# TempSensor.net
KiCad netlist of a schematic drawn in Altium Designer
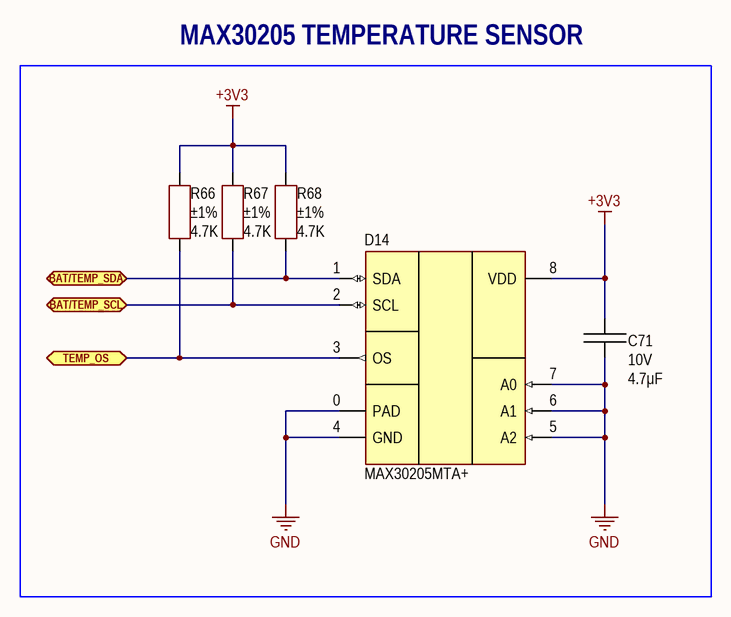
[diagram p0: TempSensor — копия.SchDoc]

(export (version "E")
  (design (tool "Eeschema 10.0.6"))
  (components
    (comp (ref "C71")
      (value "4.7μF")
      (footprint "CAP: 0805")
      (description "4.7 µF ±10% 16V Ceramic Capacitor X7R 0805 (2012 Metric)")
      (fields
        (field (name "MANUFACTURER") "Yageo")
        (field (name "PARTNUMBER") "CC0805KKX7R7BB475")
        (field (name "VOLTAGE") "10V")
      )
      (libsource (lib "capacitor") (part "Ceramic_0805"))
    )
    (comp (ref "D14")
      (value "~")
      (footprint "8-TDFN")
      (description "Temperature sensor")
      (fields
        (field (name "MANUFACTURER") "Maxim Integrated")
        (field (name "VALUEMANUFACTURERPARTNUMBER") "IC temperature sensor, Human Body Temperature Sensor, ±0.1°C, , , 0...+50°C, 8-TDFN")
        (field (name "PARTNUMBER") "MAX30205MTA+")
      )
      (libsource (lib "MyLib") (part "MAX30205MTA+"))
    )
    (comp (ref "R66")
      (value "4.7K")
      (footprint "RES: 0805")
      (description "4.7 kOhms ±5% 0.125W, 1/8W Chip Resistor 0805 (2012 Metric) Moisture Resistant Thick Film")
      (fields
        (field (name "MANUFACTURER") "Yageo")
        (field (name "PARTNUMBER") "RC0805JR-074K7L")
        (field (name "TOLERANCE") "±1%")
      )
      (libsource (lib "resistor") (part "Resistor_0805"))
    )
    (comp (ref "R67")
      (value "4.7K")
      (footprint "RES: 0805")
      (description "4.7 kOhms ±5% 0.125W, 1/8W Chip Resistor 0805 (2012 Metric) Moisture Resistant Thick Film")
      (fields
        (field (name "MANUFACTURER") "Yageo")
        (field (name "PARTNUMBER") "RC0805JR-074K7L")
        (field (name "TOLERANCE") "±1%")
      )
      (libsource (lib "resistor") (part "Resistor_0805"))
    )
    (comp (ref "R68")
      (value "4.7K")
      (footprint "RES: 0805")
      (description "4.7 kOhms ±5% 0.125W, 1/8W Chip Resistor 0805 (2012 Metric) Moisture Resistant Thick Film")
      (fields
        (field (name "MANUFACTURER") "Yageo")
        (field (name "PARTNUMBER") "RC0805JR-074K7L")
        (field (name "TOLERANCE") "±1%")
      )
      (libsource (lib "resistor") (part "Resistor_0805"))
    )
  )
  (nets
    (net (code "1") (name "+3V3") (class "Default")
      (node (ref "C71") (pin "2") (pinfunction "2_2") (pintype "passive"))
      (node (ref "D14") (pin "8") (pinfunction "VDD_8") (pintype "power_in"))
      (node (ref "R66") (pin "1") (pinfunction "1_1") (pintype "passive"))
      (node (ref "R67") (pin "1") (pinfunction "1_1") (pintype "passive"))
      (node (ref "R68") (pin "1") (pinfunction "1_1") (pintype "passive"))
    )
    (net (code "2") (name "/BAT{slash}TEMP_SCL") (class "Default")
      (node (ref "D14") (pin "2") (pinfunction "SCL_2") (pintype "bidirectional"))
      (node (ref "R67") (pin "2") (pinfunction "2_2") (pintype "passive"))
    )
    (net (code "3") (name "/BAT{slash}TEMP_SDA") (class "Default")
      (node (ref "D14") (pin "1") (pinfunction "SDA_1") (pintype "bidirectional"))
      (node (ref "R68") (pin "2") (pinfunction "2_2") (pintype "passive"))
    )
    (net (code "4") (name "/TEMP_OS") (class "Default")
      (node (ref "D14") (pin "3") (pinfunction "OS_3") (pintype "output"))
      (node (ref "R66") (pin "2") (pinfunction "2_2") (pintype "passive"))
    )
    (net (code "5") (name "GND") (class "Default")
      (node (ref "C71") (pin "1") (pinfunction "1_1") (pintype "passive"))
      (node (ref "D14") (pin "0") (pinfunction "PAD_0") (pintype "power_in"))
      (node (ref "D14") (pin "4") (pinfunction "GND_4") (pintype "power_in"))
      (node (ref "D14") (pin "5") (pinfunction "A2_5") (pintype "input"))
      (node (ref "D14") (pin "6") (pinfunction "A1_6") (pintype "input"))
      (node (ref "D14") (pin "7") (pinfunction "A0_7") (pintype "input"))
    )
  )
)
